# LPDDR4.net
KiCad netlist of a schematic drawn in Altium Designer
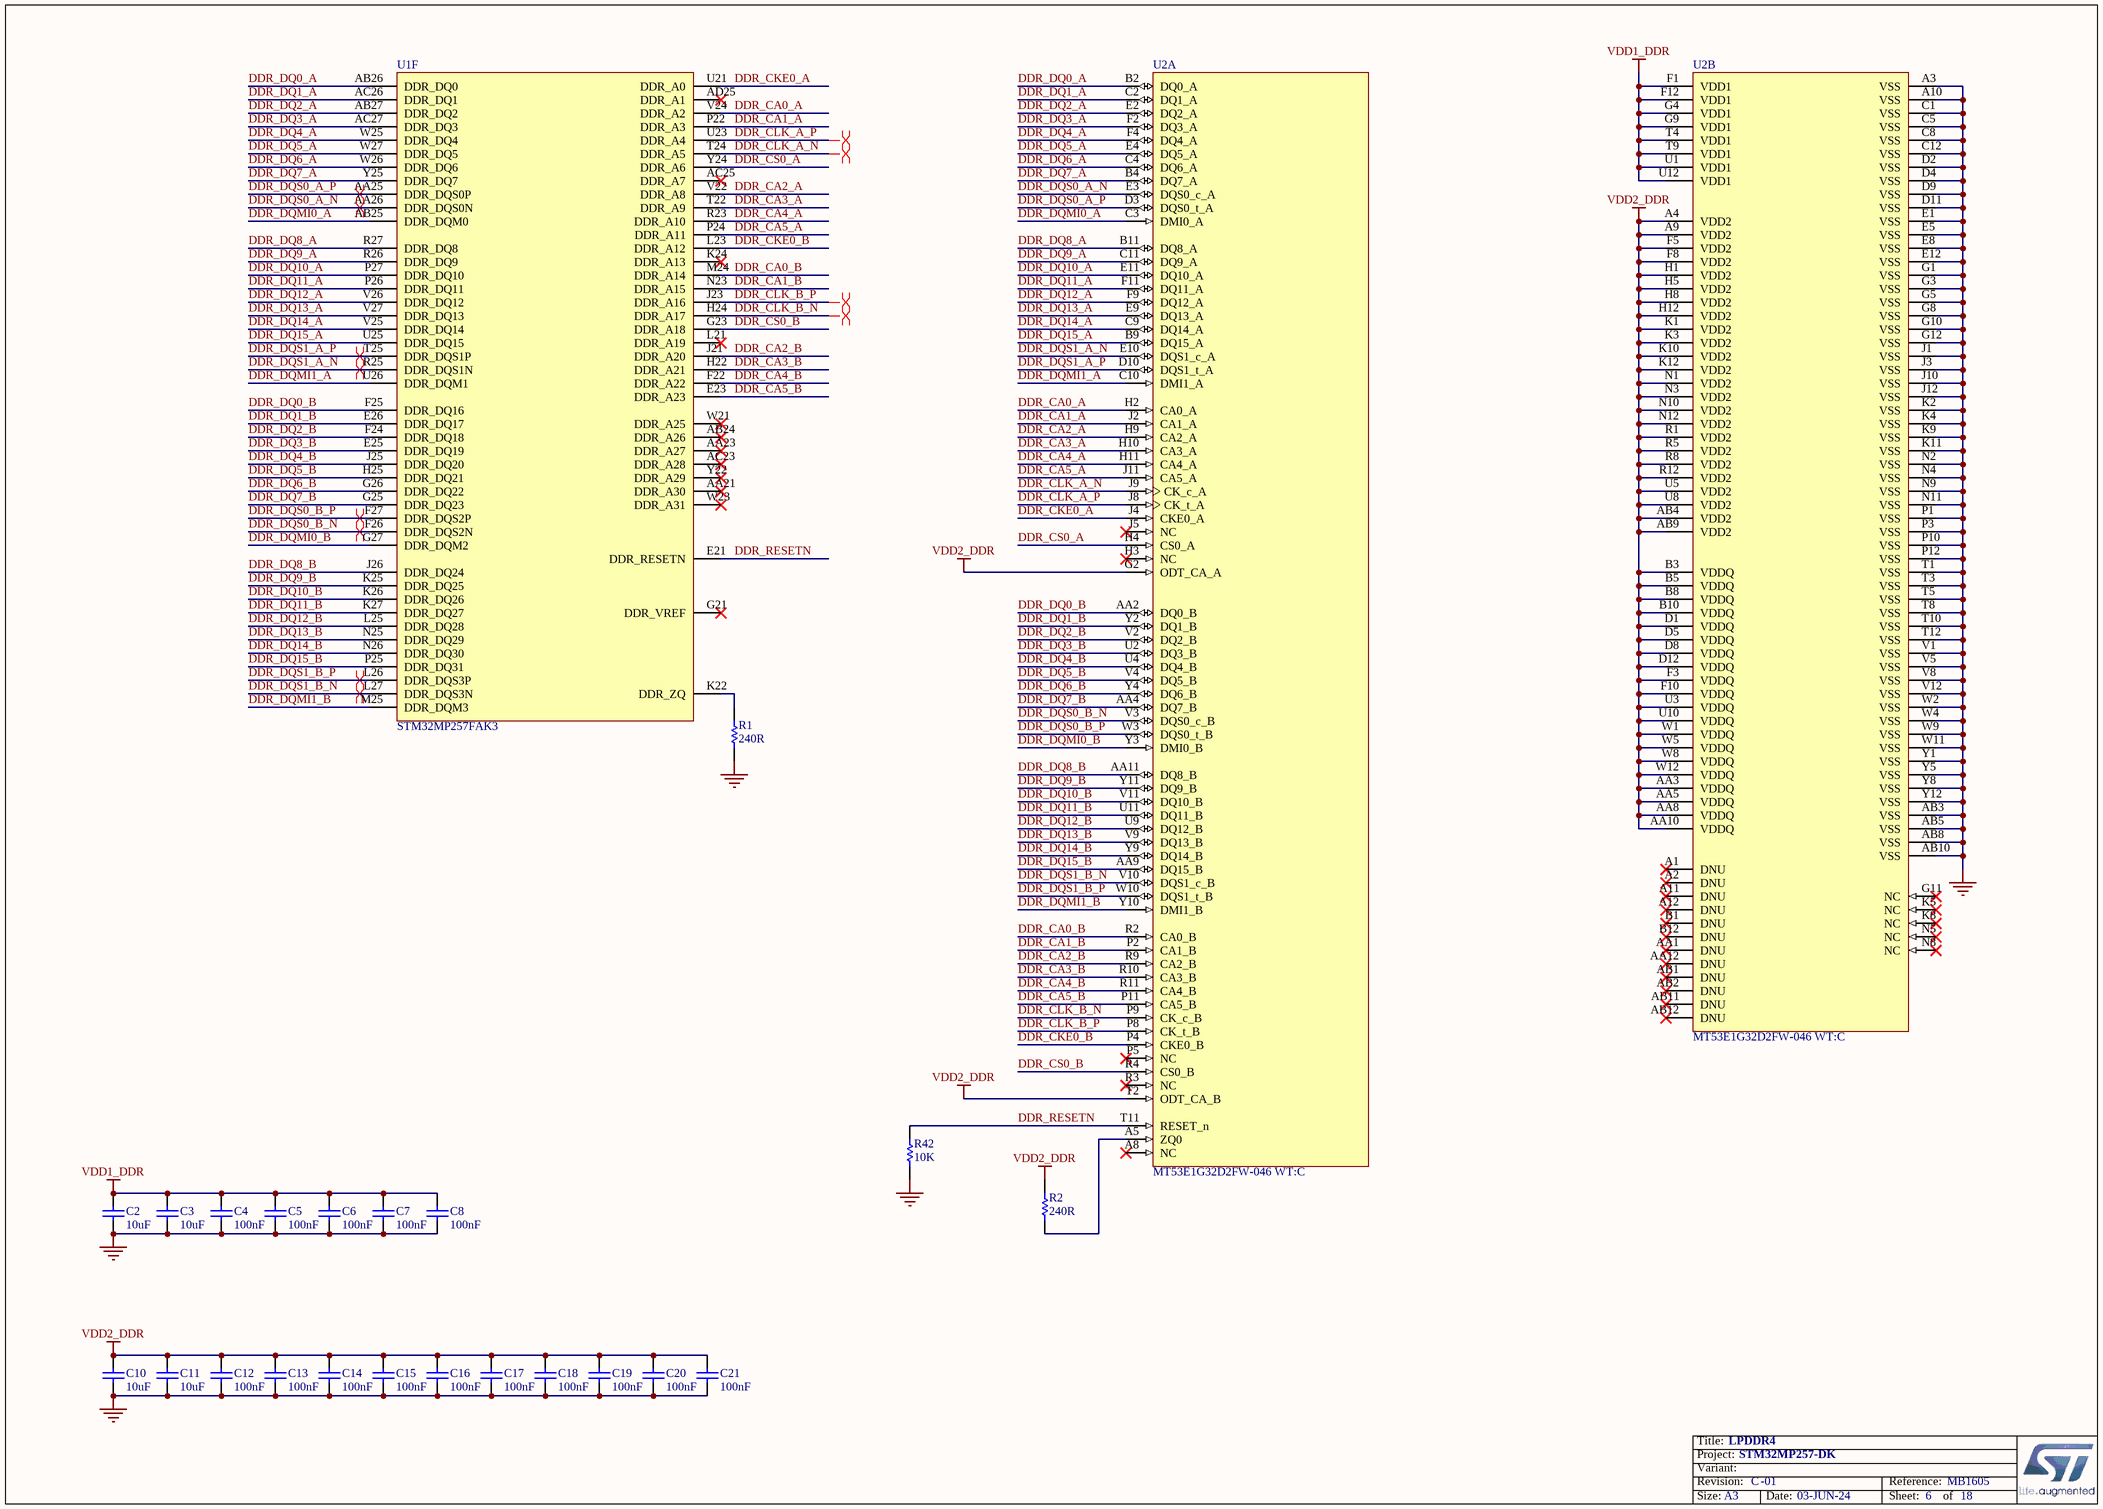
[diagram p0: LPDDR4.SchDoc]

(export (version "E")
  (design (tool "Eeschema 10.0.6"))
  (components
    (comp (ref "C2")
      (value "10uF")
      (footprint "C0603")
      (description "Capacitor, MLCC, 10uF, 6V3, X5R, 20%, 0603, T=0,8mm")
      (fields
        (field (name "INTERNAL_PART_NUMBER") "MCD-01341")
        (field (name "MANUFACTURER_PART_NUMBER") "GRM188R60J106ME47D")
        (field (name "PROVIDED_BY") "SUBCO")
      )
      (libsource (lib "MCD_PARTS_database") (part "Capacitor"))
    )
    (comp (ref "C3")
      (value "10uF")
      (footprint "C0603")
      (description "Capacitor, MLCC, 10uF, 6V3, X5R, 20%, 0603, T=0,8mm")
      (fields
        (field (name "INTERNAL_PART_NUMBER") "MCD-01341")
        (field (name "MANUFACTURER_PART_NUMBER") "GRM188R60J106ME47D")
        (field (name "PROVIDED_BY") "SUBCO")
      )
      (libsource (lib "MCD_PARTS_database") (part "Capacitor"))
    )
    (comp (ref "C4")
      (value "100nF")
      (footprint "C0402")
      (description "Capacitor, MLCC, 100nF, 16V, X7R, +/-10%, 0402, T=0.5mm")
      (fields (field (name "INTERNAL_PART_NUMBER") "MCD-00006") (field (name "MANUFACTURER") "YAGEO"))
      (libsource (lib "MCD_PARTS_database") (part "Capacitor"))
    )
    (comp (ref "C5")
      (value "100nF")
      (footprint "C0402")
      (description "Capacitor, MLCC, 100nF, 16V, X7R, +/-10%, 0402, T=0.5mm")
      (fields (field (name "INTERNAL_PART_NUMBER") "MCD-00006") (field (name "MANUFACTURER") "YAGEO"))
      (libsource (lib "MCD_PARTS_database") (part "Capacitor"))
    )
    (comp (ref "C6")
      (value "100nF")
      (footprint "C0402")
      (description "Capacitor, MLCC, 100nF, 16V, X7R, +/-10%, 0402, T=0.5mm")
      (fields (field (name "INTERNAL_PART_NUMBER") "MCD-00006") (field (name "MANUFACTURER") "YAGEO"))
      (libsource (lib "MCD_PARTS_database") (part "Capacitor"))
    )
    (comp (ref "C7")
      (value "100nF")
      (footprint "C0402")
      (description "Capacitor, MLCC, 100nF, 16V, X7R, +/-10%, 0402, T=0.5mm")
      (fields (field (name "INTERNAL_PART_NUMBER") "MCD-00006") (field (name "MANUFACTURER") "YAGEO"))
      (libsource (lib "MCD_PARTS_database") (part "Capacitor"))
    )
    (comp (ref "C8")
      (value "100nF")
      (footprint "C0402")
      (description "Capacitor, MLCC, 100nF, 16V, X7R, +/-10%, 0402, T=0.5mm")
      (fields (field (name "INTERNAL_PART_NUMBER") "MCD-00006") (field (name "MANUFACTURER") "YAGEO"))
      (libsource (lib "MCD_PARTS_database") (part "Capacitor"))
    )
    (comp (ref "C10")
      (value "10uF")
      (footprint "C0603")
      (description "Capacitor, MLCC, 10uF, 6V3, X5R, 20%, 0603, T=0,8mm")
      (fields
        (field (name "INTERNAL_PART_NUMBER") "MCD-01341")
        (field (name "MANUFACTURER_PART_NUMBER") "GRM188R60J106ME47D")
        (field (name "PROVIDED_BY") "SUBCO")
      )
      (libsource (lib "MCD_PARTS_database") (part "Capacitor"))
    )
    (comp (ref "C11")
      (value "10uF")
      (footprint "C0603")
      (description "Capacitor, MLCC, 10uF, 6V3, X5R, 20%, 0603, T=0,8mm")
      (fields
        (field (name "INTERNAL_PART_NUMBER") "MCD-01341")
        (field (name "MANUFACTURER_PART_NUMBER") "GRM188R60J106ME47D")
        (field (name "PROVIDED_BY") "SUBCO")
      )
      (libsource (lib "MCD_PARTS_database") (part "Capacitor"))
    )
    (comp (ref "C12")
      (value "100nF")
      (footprint "C0402")
      (description "Capacitor, MLCC, 100nF, 16V, X7R, +/-10%, 0402, T=0.5mm")
      (fields (field (name "INTERNAL_PART_NUMBER") "MCD-00006") (field (name "MANUFACTURER") "YAGEO"))
      (libsource (lib "MCD_PARTS_database") (part "Capacitor"))
    )
    (comp (ref "C13")
      (value "100nF")
      (footprint "C0402")
      (description "Capacitor, MLCC, 100nF, 16V, X7R, +/-10%, 0402, T=0.5mm")
      (fields (field (name "INTERNAL_PART_NUMBER") "MCD-00006") (field (name "MANUFACTURER") "YAGEO"))
      (libsource (lib "MCD_PARTS_database") (part "Capacitor"))
    )
    (comp (ref "C14")
      (value "100nF")
      (footprint "C0402")
      (description "Capacitor, MLCC, 100nF, 16V, X7R, +/-10%, 0402, T=0.5mm")
      (fields (field (name "INTERNAL_PART_NUMBER") "MCD-00006") (field (name "MANUFACTURER") "YAGEO"))
      (libsource (lib "MCD_PARTS_database") (part "Capacitor"))
    )
    (comp (ref "C15")
      (value "100nF")
      (footprint "C0402")
      (description "Capacitor, MLCC, 100nF, 16V, X7R, +/-10%, 0402, T=0.5mm")
      (fields (field (name "INTERNAL_PART_NUMBER") "MCD-00006") (field (name "MANUFACTURER") "YAGEO"))
      (libsource (lib "MCD_PARTS_database") (part "Capacitor"))
    )
    (comp (ref "C16")
      (value "100nF")
      (footprint "C0402")
      (description "Capacitor, MLCC, 100nF, 16V, X7R, +/-10%, 0402, T=0.5mm")
      (fields (field (name "INTERNAL_PART_NUMBER") "MCD-00006") (field (name "MANUFACTURER") "YAGEO"))
      (libsource (lib "MCD_PARTS_database") (part "Capacitor"))
    )
    (comp (ref "C17")
      (value "100nF")
      (footprint "C0402")
      (description "Capacitor, MLCC, 100nF, 16V, X7R, +/-10%, 0402, T=0.5mm")
      (fields (field (name "INTERNAL_PART_NUMBER") "MCD-00006") (field (name "MANUFACTURER") "YAGEO"))
      (libsource (lib "MCD_PARTS_database") (part "Capacitor"))
    )
    (comp (ref "C18")
      (value "100nF")
      (footprint "C0402")
      (description "Capacitor, MLCC, 100nF, 16V, X7R, +/-10%, 0402, T=0.5mm")
      (fields (field (name "INTERNAL_PART_NUMBER") "MCD-00006") (field (name "MANUFACTURER") "YAGEO"))
      (libsource (lib "MCD_PARTS_database") (part "Capacitor"))
    )
    (comp (ref "C19")
      (value "100nF")
      (footprint "C0402")
      (description "Capacitor, MLCC, 100nF, 16V, X7R, +/-10%, 0402, T=0.5mm")
      (fields (field (name "INTERNAL_PART_NUMBER") "MCD-00006") (field (name "MANUFACTURER") "YAGEO"))
      (libsource (lib "MCD_PARTS_database") (part "Capacitor"))
    )
    (comp (ref "C20")
      (value "100nF")
      (footprint "C0402")
      (description "Capacitor, MLCC, 100nF, 16V, X7R, +/-10%, 0402, T=0.5mm")
      (fields (field (name "INTERNAL_PART_NUMBER") "MCD-00006") (field (name "MANUFACTURER") "YAGEO"))
      (libsource (lib "MCD_PARTS_database") (part "Capacitor"))
    )
    (comp (ref "C21")
      (value "100nF")
      (footprint "C0402")
      (description "Capacitor, MLCC, 100nF, 16V, X7R, +/-10%, 0402, T=0.5mm")
      (fields (field (name "INTERNAL_PART_NUMBER") "MCD-00006") (field (name "MANUFACTURER") "YAGEO"))
      (libsource (lib "MCD_PARTS_database") (part "Capacitor"))
    )
    (comp (ref "R1")
      (value "240R")
      (footprint "R0201_H0P23")
      (description "Resistor, 240R, 0201, +/-1%, 1/20W")
      (fields (field (name "INTERNAL_PART_NUMBER") "MCD-02253") (field (name "MANUFACTURER") "YAGEO"))
      (libsource (lib "MCD_PARTS_database") (part "Resistor"))
    )
    (comp (ref "R2")
      (value "240R")
      (footprint "R0201_H0P23")
      (description "Resistor, 240R, 0201, +/-1%, 1/20W")
      (fields (field (name "INTERNAL_PART_NUMBER") "MCD-02253") (field (name "MANUFACTURER") "YAGEO"))
      (libsource (lib "MCD_PARTS_database") (part "Resistor"))
    )
    (comp (ref "R42")
      (value "10K")
      (footprint "R0402")
      (description "Resistor, 10K, 0402, +/-1%, 1/16W")
      (fields (field (name "INTERNAL_PART_NUMBER") "MCD-00053") (field (name "BMS_PART_NUMBER") "9131590"))
      (libsource (lib "MCD_PARTS_database") (part "Resistor"))
    )
    (comp (ref "U1")
      (value "STM32MP257FAK3")
      (footprint "ICC_TFBGA424_14X14_P050_H1P20_CODE-B0A2")
      (description "MPU , 2xCortex-A35@1.5GHz, Cortex-M33@400MHz, TFBGA 14x14, pitch 0.5, 648KB SRAM, With Crypto")
      (fields
        (field (name "INTERNAL_PART_NUMBER") "MCD-03375")
        (field (name "MANUFACTURER") "STMICROELECTRONICS")
      )
      (libsource (lib "MCD_PARTS_database") (part "STM32MP257FAK3"))
    )
    (comp (ref "U2")
      (value "MT53E1G32D2FW-046 WT:C")
      (footprint "ICC_TFBGA200_10X14P5_P080_H1P05_PS0P3")
      (description "Memory, LPDDR4 SDRAM,1V8, 32Gbit, 2133MHz")
      (fields (field (name "INTERNAL_PART_NUMBER") "MCD-04160") (field (name "MANUFACTURER") "MICRON"))
      (libsource (lib "MCD_PARTS_database") (part "MT53E1G32D2FW-046 WT{colon}C"))
    )
  )
  (nets
    (net (code "1") (name "/DDR_CA0_A") (class "Default")
      (node (ref "U1") (pin "V24") (pinfunction "DDR_A2_V24") (pintype "passive"))
      (node (ref "U2") (pin "H2") (pinfunction "CA0_A_H2") (pintype "input"))
    )
    (net (code "2") (name "/DDR_CA0_B") (class "Default")
      (node (ref "U1") (pin "M24") (pinfunction "DDR_A14_M24") (pintype "passive"))
      (node (ref "U2") (pin "R2") (pinfunction "CA0_B_R2") (pintype "input"))
    )
    (net (code "3") (name "/DDR_CA1_A") (class "Default")
      (node (ref "U1") (pin "P22") (pinfunction "DDR_A3_P22") (pintype "passive"))
      (node (ref "U2") (pin "J2") (pinfunction "CA1_A_J2") (pintype "input"))
    )
    (net (code "4") (name "/DDR_CA1_B") (class "Default")
      (node (ref "U1") (pin "N23") (pinfunction "DDR_A15_N23") (pintype "passive"))
      (node (ref "U2") (pin "P2") (pinfunction "CA1_B_P2") (pintype "input"))
    )
    (net (code "5") (name "/DDR_CA2_A") (class "Default")
      (node (ref "U1") (pin "V22") (pinfunction "DDR_A8_V22") (pintype "passive"))
      (node (ref "U2") (pin "H9") (pinfunction "CA2_A_H9") (pintype "input"))
    )
    (net (code "6") (name "/DDR_CA2_B") (class "Default")
      (node (ref "U1") (pin "J21") (pinfunction "DDR_A20_J21") (pintype "passive"))
      (node (ref "U2") (pin "R9") (pinfunction "CA2_B_R9") (pintype "input"))
    )
    (net (code "7") (name "/DDR_CA3_A") (class "Default")
      (node (ref "U1") (pin "T22") (pinfunction "DDR_A9_T22") (pintype "passive"))
      (node (ref "U2") (pin "H10") (pinfunction "CA3_A_H10") (pintype "input"))
    )
    (net (code "8") (name "/DDR_CA3_B") (class "Default")
      (node (ref "U1") (pin "H22") (pinfunction "DDR_A21_H22") (pintype "passive"))
      (node (ref "U2") (pin "R10") (pinfunction "CA3_B_R10") (pintype "input"))
    )
    (net (code "9") (name "/DDR_CA4_A") (class "Default")
      (node (ref "U1") (pin "R23") (pinfunction "DDR_A10_R23") (pintype "passive"))
      (node (ref "U2") (pin "H11") (pinfunction "CA4_A_H11") (pintype "input"))
    )
    (net (code "10") (name "/DDR_CA4_B") (class "Default")
      (node (ref "U1") (pin "F22") (pinfunction "DDR_A22_F22") (pintype "passive"))
      (node (ref "U2") (pin "R11") (pinfunction "CA4_B_R11") (pintype "input"))
    )
    (net (code "11") (name "/DDR_CA5_A") (class "Default")
      (node (ref "U1") (pin "P24") (pinfunction "DDR_A11_P24") (pintype "passive"))
      (node (ref "U2") (pin "J11") (pinfunction "CA5_A_J11") (pintype "input"))
    )
    (net (code "12") (name "/DDR_CA5_B") (class "Default")
      (node (ref "U1") (pin "E23") (pinfunction "DDR_A23_E23") (pintype "passive"))
      (node (ref "U2") (pin "P11") (pinfunction "CA5_B_P11") (pintype "input"))
    )
    (net (code "13") (name "/DDR_CKE0_A") (class "Default")
      (node (ref "U1") (pin "U21") (pinfunction "DDR_A0_U21") (pintype "passive"))
      (node (ref "U2") (pin "J4") (pinfunction "CKE0_A_J4") (pintype "input"))
    )
    (net (code "14") (name "/DDR_CKE0_B") (class "Default")
      (node (ref "U1") (pin "L23") (pinfunction "DDR_A12_L23") (pintype "passive"))
      (node (ref "U2") (pin "P4") (pinfunction "CKE0_B_P4") (pintype "input"))
    )
    (net (code "15") (name "/DDR_CLK_A_N") (class "Default")
      (node (ref "U1") (pin "T24") (pinfunction "DDR_A5_T24") (pintype "passive"))
      (node (ref "U2") (pin "J9") (pinfunction "CK_c_A_J9") (pintype "input"))
    )
    (net (code "16") (name "/DDR_CLK_A_P") (class "Default")
      (node (ref "U1") (pin "U23") (pinfunction "DDR_A4_U23") (pintype "passive"))
      (node (ref "U2") (pin "J8") (pinfunction "CK_t_A_J8") (pintype "input"))
    )
    (net (code "17") (name "/DDR_CLK_B_N") (class "Default")
      (node (ref "U1") (pin "H24") (pinfunction "DDR_A17_H24") (pintype "passive"))
      (node (ref "U2") (pin "P9") (pinfunction "CK_c_B_P9") (pintype "input"))
    )
    (net (code "18") (name "/DDR_CLK_B_P") (class "Default")
      (node (ref "U1") (pin "J23") (pinfunction "DDR_A16_J23") (pintype "passive"))
      (node (ref "U2") (pin "P8") (pinfunction "CK_t_B_P8") (pintype "input"))
    )
    (net (code "19") (name "/DDR_CS0_A") (class "Default")
      (node (ref "U1") (pin "Y24") (pinfunction "DDR_A6_Y24") (pintype "passive"))
      (node (ref "U2") (pin "H4") (pinfunction "CS0_A_H4") (pintype "input"))
    )
    (net (code "20") (name "/DDR_CS0_B") (class "Default")
      (node (ref "U1") (pin "G23") (pinfunction "DDR_A18_G23") (pintype "passive"))
      (node (ref "U2") (pin "R4") (pinfunction "CS0_B_R4") (pintype "input"))
    )
    (net (code "21") (name "/DDR_DQ0_A") (class "Default")
      (node (ref "U1") (pin "AB26") (pinfunction "DDR_DQ0_AB26") (pintype "passive"))
      (node (ref "U2") (pin "B2") (pinfunction "DQ0_A_B2") (pintype "bidirectional"))
    )
    (net (code "22") (name "/DDR_DQ0_B") (class "Default")
      (node (ref "U1") (pin "F25") (pinfunction "DDR_DQ16_F25") (pintype "passive"))
      (node (ref "U2") (pin "AA2") (pinfunction "DQ0_B_AA2") (pintype "bidirectional"))
    )
    (net (code "23") (name "/DDR_DQ1_A") (class "Default")
      (node (ref "U1") (pin "AC26") (pinfunction "DDR_DQ1_AC26") (pintype "passive"))
      (node (ref "U2") (pin "C2") (pinfunction "DQ1_A_C2") (pintype "bidirectional"))
    )
    (net (code "24") (name "/DDR_DQ1_B") (class "Default")
      (node (ref "U1") (pin "E26") (pinfunction "DDR_DQ17_E26") (pintype "passive"))
      (node (ref "U2") (pin "Y2") (pinfunction "DQ1_B_Y2") (pintype "bidirectional"))
    )
    (net (code "25") (name "/DDR_DQ2_A") (class "Default")
      (node (ref "U1") (pin "AB27") (pinfunction "DDR_DQ2_AB27") (pintype "passive"))
      (node (ref "U2") (pin "E2") (pinfunction "DQ2_A_E2") (pintype "bidirectional"))
    )
    (net (code "26") (name "/DDR_DQ2_B") (class "Default")
      (node (ref "U1") (pin "F24") (pinfunction "DDR_DQ18_F24") (pintype "passive"))
      (node (ref "U2") (pin "V2") (pinfunction "DQ2_B_V2") (pintype "bidirectional"))
    )
    (net (code "27") (name "/DDR_DQ3_A") (class "Default")
      (node (ref "U1") (pin "AC27") (pinfunction "DDR_DQ3_AC27") (pintype "passive"))
      (node (ref "U2") (pin "F2") (pinfunction "DQ3_A_F2") (pintype "bidirectional"))
    )
    (net (code "28") (name "/DDR_DQ3_B") (class "Default")
      (node (ref "U1") (pin "E25") (pinfunction "DDR_DQ19_E25") (pintype "passive"))
      (node (ref "U2") (pin "U2") (pinfunction "DQ3_B_U2") (pintype "bidirectional"))
    )
    (net (code "29") (name "/DDR_DQ4_A") (class "Default")
      (node (ref "U1") (pin "W25") (pinfunction "DDR_DQ4_W25") (pintype "passive"))
      (node (ref "U2") (pin "F4") (pinfunction "DQ4_A_F4") (pintype "bidirectional"))
    )
    (net (code "30") (name "/DDR_DQ4_B") (class "Default")
      (node (ref "U1") (pin "J25") (pinfunction "DDR_DQ20_J25") (pintype "passive"))
      (node (ref "U2") (pin "U4") (pinfunction "DQ4_B_U4") (pintype "bidirectional"))
    )
    (net (code "31") (name "/DDR_DQ5_A") (class "Default")
      (node (ref "U1") (pin "W27") (pinfunction "DDR_DQ5_W27") (pintype "passive"))
      (node (ref "U2") (pin "E4") (pinfunction "DQ5_A_E4") (pintype "bidirectional"))
    )
    (net (code "32") (name "/DDR_DQ5_B") (class "Default")
      (node (ref "U1") (pin "H25") (pinfunction "DDR_DQ21_H25") (pintype "passive"))
      (node (ref "U2") (pin "V4") (pinfunction "DQ5_B_V4") (pintype "bidirectional"))
    )
    (net (code "33") (name "/DDR_DQ6_A") (class "Default")
      (node (ref "U1") (pin "W26") (pinfunction "DDR_DQ6_W26") (pintype "passive"))
      (node (ref "U2") (pin "C4") (pinfunction "DQ6_A_C4") (pintype "bidirectional"))
    )
    (net (code "34") (name "/DDR_DQ6_B") (class "Default")
      (node (ref "U1") (pin "G26") (pinfunction "DDR_DQ22_G26") (pintype "passive"))
      (node (ref "U2") (pin "Y4") (pinfunction "DQ6_B_Y4") (pintype "bidirectional"))
    )
    (net (code "35") (name "/DDR_DQ7_A") (class "Default")
      (node (ref "U1") (pin "Y25") (pinfunction "DDR_DQ7_Y25") (pintype "passive"))
      (node (ref "U2") (pin "B4") (pinfunction "DQ7_A_B4") (pintype "bidirectional"))
    )
    (net (code "36") (name "/DDR_DQ7_B") (class "Default")
      (node (ref "U1") (pin "G25") (pinfunction "DDR_DQ23_G25") (pintype "passive"))
      (node (ref "U2") (pin "AA4") (pinfunction "DQ7_B_AA4") (pintype "bidirectional"))
    )
    (net (code "37") (name "/DDR_DQ8_A") (class "Default")
      (node (ref "U1") (pin "R27") (pinfunction "DDR_DQ8_R27") (pintype "passive"))
      (node (ref "U2") (pin "B11") (pinfunction "DQ8_A_B11") (pintype "bidirectional"))
    )
    (net (code "38") (name "/DDR_DQ8_B") (class "Default")
      (node (ref "U1") (pin "J26") (pinfunction "DDR_DQ24_J26") (pintype "passive"))
      (node (ref "U2") (pin "AA11") (pinfunction "DQ8_B_AA11") (pintype "bidirectional"))
    )
    (net (code "39") (name "/DDR_DQ9_A") (class "Default")
      (node (ref "U1") (pin "R26") (pinfunction "DDR_DQ9_R26") (pintype "passive"))
      (node (ref "U2") (pin "C11") (pinfunction "DQ9_A_C11") (pintype "bidirectional"))
    )
    (net (code "40") (name "/DDR_DQ9_B") (class "Default")
      (node (ref "U1") (pin "K25") (pinfunction "DDR_DQ25_K25") (pintype "passive"))
      (node (ref "U2") (pin "Y11") (pinfunction "DQ9_B_Y11") (pintype "bidirectional"))
    )
    (net (code "41") (name "/DDR_DQ10_A") (class "Default")
      (node (ref "U1") (pin "P27") (pinfunction "DDR_DQ10_P27") (pintype "passive"))
      (node (ref "U2") (pin "E11") (pinfunction "DQ10_A_E11") (pintype "bidirectional"))
    )
    (net (code "42") (name "/DDR_DQ10_B") (class "Default")
      (node (ref "U1") (pin "K26") (pinfunction "DDR_DQ26_K26") (pintype "passive"))
      (node (ref "U2") (pin "V11") (pinfunction "DQ10_B_V11") (pintype "bidirectional"))
    )
    (net (code "43") (name "/DDR_DQ11_A") (class "Default")
      (node (ref "U1") (pin "P26") (pinfunction "DDR_DQ11_P26") (pintype "passive"))
      (node (ref "U2") (pin "F11") (pinfunction "DQ11_A_F11") (pintype "bidirectional"))
    )
    (net (code "44") (name "/DDR_DQ11_B") (class "Default")
      (node (ref "U1") (pin "K27") (pinfunction "DDR_DQ27_K27") (pintype "passive"))
      (node (ref "U2") (pin "U11") (pinfunction "DQ11_B_U11") (pintype "bidirectional"))
    )
    (net (code "45") (name "/DDR_DQ12_A") (class "Default")
      (node (ref "U1") (pin "V26") (pinfunction "DDR_DQ12_V26") (pintype "passive"))
      (node (ref "U2") (pin "F9") (pinfunction "DQ12_A_F9") (pintype "bidirectional"))
    )
    (net (code "46") (name "/DDR_DQ12_B") (class "Default")
      (node (ref "U1") (pin "L25") (pinfunction "DDR_DQ28_L25") (pintype "passive"))
      (node (ref "U2") (pin "U9") (pinfunction "DQ12_B_U9") (pintype "bidirectional"))
    )
    (net (code "47") (name "/DDR_DQ13_A") (class "Default")
      (node (ref "U1") (pin "V27") (pinfunction "DDR_DQ13_V27") (pintype "passive"))
      (node (ref "U2") (pin "E9") (pinfunction "DQ13_A_E9") (pintype "bidirectional"))
    )
    (net (code "48") (name "/DDR_DQ13_B") (class "Default")
      (node (ref "U1") (pin "N25") (pinfunction "DDR_DQ29_N25") (pintype "passive"))
      (node (ref "U2") (pin "V9") (pinfunction "DQ13_B_V9") (pintype "bidirectional"))
    )
    (net (code "49") (name "/DDR_DQ14_A") (class "Default")
      (node (ref "U1") (pin "V25") (pinfunction "DDR_DQ14_V25") (pintype "passive"))
      (node (ref "U2") (pin "C9") (pinfunction "DQ14_A_C9") (pintype "bidirectional"))
    )
    (net (code "50") (name "/DDR_DQ14_B") (class "Default")
      (node (ref "U1") (pin "N26") (pinfunction "DDR_DQ30_N26") (pintype "passive"))
      (node (ref "U2") (pin "Y9") (pinfunction "DQ14_B_Y9") (pintype "bidirectional"))
    )
    (net (code "51") (name "/DDR_DQ15_A") (class "Default")
      (node (ref "U1") (pin "U25") (pinfunction "DDR_DQ15_U25") (pintype "passive"))
      (node (ref "U2") (pin "B9") (pinfunction "DQ15_A_B9") (pintype "bidirectional"))
    )
    (net (code "52") (name "/DDR_DQ15_B") (class "Default")
      (node (ref "U1") (pin "P25") (pinfunction "DDR_DQ31_P25") (pintype "passive"))
      (node (ref "U2") (pin "AA9") (pinfunction "DQ15_B_AA9") (pintype "bidirectional"))
    )
    (net (code "53") (name "/DDR_DQMI0_A") (class "Default")
      (node (ref "U1") (pin "AB25") (pinfunction "DDR_DQM0_AB25") (pintype "passive"))
      (node (ref "U2") (pin "C3") (pinfunction "DMI0_A_C3") (pintype "input"))
    )
    (net (code "54") (name "/DDR_DQMI0_B") (class "Default")
      (node (ref "U1") (pin "G27") (pinfunction "DDR_DQM2_G27") (pintype "passive"))
      (node (ref "U2") (pin "Y3") (pinfunction "DMI0_B_Y3") (pintype "input"))
    )
    (net (code "55") (name "/DDR_DQMI1_A") (class "Default")
      (node (ref "U1") (pin "U26") (pinfunction "DDR_DQM1_U26") (pintype "passive"))
      (node (ref "U2") (pin "C10") (pinfunction "DMI1_A_C10") (pintype "input"))
    )
    (net (code "56") (name "/DDR_DQMI1_B") (class "Default")
      (node (ref "U1") (pin "M25") (pinfunction "DDR_DQM3_M25") (pintype "passive"))
      (node (ref "U2") (pin "Y10") (pinfunction "DMI1_B_Y10") (pintype "input"))
    )
    (net (code "57") (name "/DDR_DQS0_A_N") (class "Default")
      (node (ref "U1") (pin "AA26") (pinfunction "DDR_DQS0N_AA26") (pintype "passive"))
      (node (ref "U2") (pin "E3") (pinfunction "DQS0_c_A_E3") (pintype "bidirectional"))
    )
    (net (code "58") (name "/DDR_DQS0_A_P") (class "Default")
      (node (ref "U1") (pin "AA25") (pinfunction "DDR_DQS0P_AA25") (pintype "passive"))
      (node (ref "U2") (pin "D3") (pinfunction "DQS0_t_A_D3") (pintype "bidirectional"))
    )
    (net (code "59") (name "/DDR_DQS0_B_N") (class "Default")
      (node (ref "U1") (pin "F26") (pinfunction "DDR_DQS2N_F26") (pintype "passive"))
      (node (ref "U2") (pin "V3") (pinfunction "DQS0_c_B_V3") (pintype "bidirectional"))
    )
    (net (code "60") (name "/DDR_DQS0_B_P") (class "Default")
      (node (ref "U1") (pin "F27") (pinfunction "DDR_DQS2P_F27") (pintype "passive"))
      (node (ref "U2") (pin "W3") (pinfunction "DQS0_t_B_W3") (pintype "bidirectional"))
    )
    (net (code "61") (name "/DDR_DQS1_A_N") (class "Default")
      (node (ref "U1") (pin "R25") (pinfunction "DDR_DQS1N_R25") (pintype "passive"))
      (node (ref "U2") (pin "E10") (pinfunction "DQS1_c_A_E10") (pintype "bidirectional"))
    )
    (net (code "62") (name "/DDR_DQS1_A_P") (class "Default")
      (node (ref "U1") (pin "T25") (pinfunction "DDR_DQS1P_T25") (pintype "passive"))
      (node (ref "U2") (pin "D10") (pinfunction "DQS1_t_A_D10") (pintype "bidirectional"))
    )
    (net (code "63") (name "/DDR_DQS1_B_N") (class "Default")
      (node (ref "U1") (pin "L27") (pinfunction "DDR_DQS3N_L27") (pintype "passive"))
      (node (ref "U2") (pin "V10") (pinfunction "DQS1_c_B_V10") (pintype "bidirectional"))
    )
    (net (code "64") (name "/DDR_DQS1_B_P") (class "Default")
      (node (ref "U1") (pin "L26") (pinfunction "DDR_DQS3P_L26") (pintype "passive"))
      (node (ref "U2") (pin "W10") (pinfunction "DQS1_t_B_W10") (pintype "bidirectional"))
    )
    (net (code "65") (name "/DDR_RESETN") (class "Default")
      (node (ref "R42") (pin "2") (pinfunction "2_2") (pintype "passive"))
      (node (ref "U1") (pin "E21") (pinfunction "DDR_RESETN_E21") (pintype "passive"))
      (node (ref "U2") (pin "T11") (pinfunction "RESET_n_T11") (pintype "input"))
    )
    (net (code "66") (name "GND") (class "Default")
      (node (ref "C10") (pin "1") (pinfunction "1_1") (pintype "passive"))
      (node (ref "C11") (pin "1") (pinfunction "1_1") (pintype "passive"))
      (node (ref "C12") (pin "2") (pinfunction "2_2") (pintype "passive"))
      (node (ref "C13") (pin "2") (pinfunction "2_2") (pintype "passive"))
      (node (ref "C14") (pin "2") (pinfunction "2_2") (pintype "passive"))
      (node (ref "C15") (pin "2") (pinfunction "2_2") (pintype "passive"))
      (node (ref "C16") (pin "2") (pinfunction "2_2") (pintype "passive"))
      (node (ref "C17") (pin "2") (pinfunction "2_2") (pintype "passive"))
      (node (ref "C18") (pin "2") (pinfunction "2_2") (pintype "passive"))
      (node (ref "C19") (pin "2") (pinfunction "2_2") (pintype "passive"))
      (node (ref "C2") (pin "1") (pinfunction "1_1") (pintype "passive"))
      (node (ref "C20") (pin "2") (pinfunction "2_2") (pintype "passive"))
      (node (ref "C21") (pin "2") (pinfunction "2_2") (pintype "passive"))
      (node (ref "C3") (pin "1") (pinfunction "1_1") (pintype "passive"))
      (node (ref "C4") (pin "2") (pinfunction "2_2") (pintype "passive"))
      (node (ref "C5") (pin "2") (pinfunction "2_2") (pintype "passive"))
      (node (ref "C6") (pin "2") (pinfunction "2_2") (pintype "passive"))
      (node (ref "C7") (pin "2") (pinfunction "2_2") (pintype "passive"))
      (node (ref "C8") (pin "2") (pinfunction "2_2") (pintype "passive"))
      (node (ref "R1") (pin "1") (pinfunction "1_1") (pintype "passive"))
      (node (ref "R42") (pin "1") (pinfunction "1_1") (pintype "passive"))
      (node (ref "U2") (pin "A10") (pinfunction "VSS_A10") (pintype "power_in"))
      (node (ref "U2") (pin "A3") (pinfunction "VSS_A3") (pintype "power_in"))
      (node (ref "U2") (pin "AB10") (pinfunction "VSS_AB10") (pintype "passive"))
      (node (ref "U2") (pin "AB3") (pinfunction "VSS_AB3") (pintype "passive"))
      (node (ref "U2") (pin "AB5") (pinfunction "VSS_AB5") (pintype "passive"))
      (node (ref "U2") (pin "AB8") (pinfunction "VSS_AB8") (pintype "passive"))
      (node (ref "U2") (pin "C1") (pinfunction "VSS_C1") (pintype "power_in"))
      (node (ref "U2") (pin "C12") (pinfunction "VSS_C12") (pintype "power_in"))
      (node (ref "U2") (pin "C5") (pinfunction "VSS_C5") (pintype "power_in"))
      (node (ref "U2") (pin "C8") (pinfunction "VSS_C8") (pintype "power_in"))
      (node (ref "U2") (pin "D11") (pinfunction "VSS_D11") (pintype "power_in"))
      (node (ref "U2") (pin "D2") (pinfunction "VSS_D2") (pintype "power_in"))
      (node (ref "U2") (pin "D4") (pinfunction "VSS_D4") (pintype "power_in"))
      (node (ref "U2") (pin "D9") (pinfunction "VSS_D9") (pintype "power_in"))
      (node (ref "U2") (pin "E1") (pinfunction "VSS_E1") (pintype "power_in"))
      (node (ref "U2") (pin "E12") (pinfunction "VSS_E12") (pintype "power_in"))
      (node (ref "U2") (pin "E5") (pinfunction "VSS_E5") (pintype "power_in"))
      (node (ref "U2") (pin "E8") (pinfunction "VSS_E8") (pintype "power_in"))
      (node (ref "U2") (pin "G1") (pinfunction "VSS_G1") (pintype "power_in"))
      (node (ref "U2") (pin "G10") (pinfunction "VSS_G10") (pintype "power_in"))
      (node (ref "U2") (pin "G12") (pinfunction "VSS_G12") (pintype "power_in"))
      (node (ref "U2") (pin "G3") (pinfunction "VSS_G3") (pintype "power_in"))
      (node (ref "U2") (pin "G5") (pinfunction "VSS_G5") (pintype "power_in"))
      (node (ref "U2") (pin "G8") (pinfunction "VSS_G8") (pintype "power_in"))
      (node (ref "U2") (pin "J1") (pinfunction "VSS_J1") (pintype "power_in"))
      (node (ref "U2") (pin "J10") (pinfunction "VSS_J10") (pintype "power_in"))
      (node (ref "U2") (pin "J12") (pinfunction "VSS_J12") (pintype "power_in"))
      (node (ref "U2") (pin "J3") (pinfunction "VSS_J3") (pintype "power_in"))
      (node (ref "U2") (pin "K11") (pinfunction "VSS_K11") (pintype "passive"))
      (node (ref "U2") (pin "K2") (pinfunction "VSS_K2") (pintype "power_in"))
      (node (ref "U2") (pin "K4") (pinfunction "VSS_K4") (pintype "power_in"))
      (node (ref "U2") (pin "K9") (pinfunction "VSS_K9") (pintype "power_in"))
      (node (ref "U2") (pin "N11") (pinfunction "VSS_N11") (pintype "passive"))
      (node (ref "U2") (pin "N2") (pinfunction "VSS_N2") (pintype "passive"))
      (node (ref "U2") (pin "N4") (pinfunction "VSS_N4") (pintype "passive"))
      (node (ref "U2") (pin "N9") (pinfunction "VSS_N9") (pintype "passive"))
      (node (ref "U2") (pin "P1") (pinfunction "VSS_P1") (pintype "passive"))
      (node (ref "U2") (pin "P10") (pinfunction "VSS_P10") (pintype "power_in"))
      (node (ref "U2") (pin "P12") (pinfunction "VSS_P12") (pintype "passive"))
      (node (ref "U2") (pin "P3") (pinfunction "VSS_P3") (pintype "power_in"))
      (node (ref "U2") (pin "T1") (pinfunction "VSS_T1") (pintype "passive"))
      (node (ref "U2") (pin "T10") (pinfunction "VSS_T10") (pintype "passive"))
      (node (ref "U2") (pin "T12") (pinfunction "VSS_T12") (pintype "passive"))
      (node (ref "U2") (pin "T3") (pinfunction "VSS_T3") (pintype "passive"))
      (node (ref "U2") (pin "T5") (pinfunction "VSS_T5") (pintype "passive"))
      (node (ref "U2") (pin "T8") (pinfunction "VSS_T8") (pintype "passive"))
      (node (ref "U2") (pin "V1") (pinfunction "VSS_V1") (pintype "power_in"))
      (node (ref "U2") (pin "V12") (pinfunction "VSS_V12") (pintype "passive"))
      (node (ref "U2") (pin "V5") (pinfunction "VSS_V5") (pintype "power_in"))
      (node (ref "U2") (pin "V8") (pinfunction "VSS_V8") (pintype "passive"))
      (node (ref "U2") (pin "W11") (pinfunction "VSS_W11") (pintype "passive"))
      (node (ref "U2") (pin "W2") (pinfunction "VSS_W2") (pintype "passive"))
      (node (ref "U2") (pin "W4") (pinfunction "VSS_W4") (pintype "passive"))
      (node (ref "U2") (pin "W9") (pinfunction "VSS_W9") (pintype "passive"))
      (node (ref "U2") (pin "Y1") (pinfunction "VSS_Y1") (pintype "passive"))
      (node (ref "U2") (pin "Y12") (pinfunction "VSS_Y12") (pintype "passive"))
      (node (ref "U2") (pin "Y5") (pinfunction "VSS_Y5") (pintype "passive"))
      (node (ref "U2") (pin "Y8") (pinfunction "VSS_Y8") (pintype "passive"))
    )
    (net (code "67") (name "Net-(U1F-DDR_ZQ)") (class "Default")
      (node (ref "R1") (pin "2") (pinfunction "2_2") (pintype "passive"))
      (node (ref "U1") (pin "K22") (pinfunction "DDR_ZQ_K22") (pintype "passive"))
    )
    (net (code "68") (name "Net-(U2A-ZQ0)") (class "Default")
      (node (ref "R2") (pin "1") (pinfunction "1_1") (pintype "passive"))
      (node (ref "U2") (pin "A5") (pinfunction "ZQ0_A5") (pintype "input"))
    )
    (net (code "69") (name "VDD1_DDR") (class "Default")
      (node (ref "C2") (pin "2") (pinfunction "2_2") (pintype "passive"))
      (node (ref "C3") (pin "2") (pinfunction "2_2") (pintype "passive"))
      (node (ref "C4") (pin "1") (pinfunction "1_1") (pintype "passive"))
      (node (ref "C5") (pin "1") (pinfunction "1_1") (pintype "passive"))
      (node (ref "C6") (pin "1") (pinfunction "1_1") (pintype "passive"))
      (node (ref "C7") (pin "1") (pinfunction "1_1") (pintype "passive"))
      (node (ref "C8") (pin "1") (pinfunction "1_1") (pintype "passive"))
      (node (ref "U2") (pin "F1") (pinfunction "VDD1_F1") (pintype "power_in"))
      (node (ref "U2") (pin "F12") (pinfunction "VDD1_F12") (pintype "power_in"))
      (node (ref "U2") (pin "G4") (pinfunction "VDD1_G4") (pintype "power_in"))
      (node (ref "U2") (pin "G9") (pinfunction "VDD1_G9") (pintype "power_in"))
      (node (ref "U2") (pin "T4") (pinfunction "VDD1_T4") (pintype "power_in"))
      (node (ref "U2") (pin "T9") (pinfunction "VDD1_T9") (pintype "power_in"))
      (node (ref "U2") (pin "U1") (pinfunction "VDD1_U1") (pintype "power_in"))
      (node (ref "U2") (pin "U12") (pinfunction "VDD1_U12") (pintype "power_in"))
    )
    (net (code "70") (name "VDD2_DDR") (class "Default")
      (node (ref "C10") (pin "2") (pinfunction "2_2") (pintype "passive"))
      (node (ref "C11") (pin "2") (pinfunction "2_2") (pintype "passive"))
      (node (ref "C12") (pin "1") (pinfunction "1_1") (pintype "passive"))
      (node (ref "C13") (pin "1") (pinfunction "1_1") (pintype "passive"))
      (node (ref "C14") (pin "1") (pinfunction "1_1") (pintype "passive"))
      (node (ref "C15") (pin "1") (pinfunction "1_1") (pintype "passive"))
      (node (ref "C16") (pin "1") (pinfunction "1_1") (pintype "passive"))
      (node (ref "C17") (pin "1") (pinfunction "1_1") (pintype "passive"))
      (node (ref "C18") (pin "1") (pinfunction "1_1") (pintype "passive"))
      (node (ref "C19") (pin "1") (pinfunction "1_1") (pintype "passive"))
      (node (ref "C20") (pin "1") (pinfunction "1_1") (pintype "passive"))
      (node (ref "C21") (pin "1") (pinfunction "1_1") (pintype "passive"))
      (node (ref "R2") (pin "2") (pinfunction "2_2") (pintype "passive"))
      (node (ref "U2") (pin "A4") (pinfunction "VDD2_A4") (pintype "power_in"))
      (node (ref "U2") (pin "A9") (pinfunction "VDD2_A9") (pintype "power_in"))
      (node (ref "U2") (pin "AA10") (pinfunction "VDDQ_AA10") (pintype "power_in"))
      (node (ref "U2") (pin "AA3") (pinfunction "VDDQ_AA3") (pintype "power_in"))
      (node (ref "U2") (pin "AA5") (pinfunction "VDDQ_AA5") (pintype "power_in"))
      (node (ref "U2") (pin "AA8") (pinfunction "VDDQ_AA8") (pintype "power_in"))
      (node (ref "U2") (pin "AB4") (pinfunction "VDD2_AB4") (pintype "power_in"))
      (node (ref "U2") (pin "AB9") (pinfunction "VDD2_AB9") (pintype "power_in"))
      (node (ref "U2") (pin "B10") (pinfunction "VDDQ_B10") (pintype "power_in"))
      (node (ref "U2") (pin "B3") (pinfunction "VDDQ_B3") (pintype "power_in"))
      (node (ref "U2") (pin "B5") (pinfunction "VDDQ_B5") (pintype "power_in"))
      (node (ref "U2") (pin "B8") (pinfunction "VDDQ_B8") (pintype "power_in"))
      (node (ref "U2") (pin "D1") (pinfunction "VDDQ_D1") (pintype "power_in"))
      (node (ref "U2") (pin "D12") (pinfunction "VDDQ_D12") (pintype "power_in"))
      (node (ref "U2") (pin "D5") (pinfunction "VDDQ_D5") (pintype "power_in"))
      (node (ref "U2") (pin "D8") (pinfunction "VDDQ_D8") (pintype "power_in"))
      (node (ref "U2") (pin "F10") (pinfunction "VDDQ_F10") (pintype "power_in"))
      (node (ref "U2") (pin "F3") (pinfunction "VDDQ_F3") (pintype "power_in"))
      (node (ref "U2") (pin "F5") (pinfunction "VDD2_F5") (pintype "power_in"))
      (node (ref "U2") (pin "F8") (pinfunction "VDD2_F8") (pintype "power_in"))
      (node (ref "U2") (pin "G2") (pinfunction "ODT_CA_A_G2") (pintype "input"))
      (node (ref "U2") (pin "H1") (pinfunction "VDD2_H1") (pintype "power_in"))
      (node (ref "U2") (pin "H12") (pinfunction "VDD2_H12") (pintype "power_in"))
      (node (ref "U2") (pin "H5") (pinfunction "VDD2_H5") (pintype "power_in"))
      (node (ref "U2") (pin "H8") (pinfunction "VDD2_H8") (pintype "power_in"))
      (node (ref "U2") (pin "K1") (pinfunction "VDD2_K1") (pintype "power_in"))
      (node (ref "U2") (pin "K10") (pinfunction "VDD2_K10") (pintype "power_in"))
      (node (ref "U2") (pin "K12") (pinfunction "VDD2_K12") (pintype "power_in"))
      (node (ref "U2") (pin "K3") (pinfunction "VDD2_K3") (pintype "power_in"))
      (node (ref "U2") (pin "N1") (pinfunction "VDD2_N1") (pintype "power_in"))
      (node (ref "U2") (pin "N10") (pinfunction "VDD2_N10") (pintype "power_in"))
      (node (ref "U2") (pin "N12") (pinfunction "VDD2_N12") (pintype "power_in"))
      (node (ref "U2") (pin "N3") (pinfunction "VDD2_N3") (pintype "power_in"))
      (node (ref "U2") (pin "R1") (pinfunction "VDD2_R1") (pintype "power_in"))
      (node (ref "U2") (pin "R12") (pinfunction "VDD2_R12") (pintype "power_in"))
      (node (ref "U2") (pin "R5") (pinfunction "VDD2_R5") (pintype "power_in"))
      (node (ref "U2") (pin "R8") (pinfunction "VDD2_R8") (pintype "power_in"))
      (node (ref "U2") (pin "T2") (pinfunction "ODT_CA_B_T2") (pintype "input"))
      (node (ref "U2") (pin "U10") (pinfunction "VDDQ_U10") (pintype "power_in"))
      (node (ref "U2") (pin "U3") (pinfunction "VDDQ_U3") (pintype "power_in"))
      (node (ref "U2") (pin "U5") (pinfunction "VDD2_U5") (pintype "power_in"))
      (node (ref "U2") (pin "U8") (pinfunction "VDD2_U8") (pintype "power_in"))
      (node (ref "U2") (pin "W1") (pinfunction "VDDQ_W1") (pintype "power_in"))
      (node (ref "U2") (pin "W12") (pinfunction "VDDQ_W12") (pintype "power_in"))
      (node (ref "U2") (pin "W5") (pinfunction "VDDQ_W5") (pintype "power_in"))
      (node (ref "U2") (pin "W8") (pinfunction "VDDQ_W8") (pintype "power_in"))
    )
    (net (code "71") (name "unconnected-(U1F-DDR_A1-PadAD25)") (class "Default")
      (node (ref "U1") (pin "AD25") (pinfunction "DDR_A1_AD25") (pintype "passive+no_connect"))
    )
    (net (code "72") (name "unconnected-(U1F-DDR_A7-PadAC25)") (class "Default")
      (node (ref "U1") (pin "AC25") (pinfunction "DDR_A7_AC25") (pintype "passive+no_connect"))
    )
    (net (code "73") (name "unconnected-(U1F-DDR_A13-PadK24)") (class "Default")
      (node (ref "U1") (pin "K24") (pinfunction "DDR_A13_K24") (pintype "passive+no_connect"))
    )
    (net (code "74") (name "unconnected-(U1F-DDR_A19-PadL21)") (class "Default")
      (node (ref "U1") (pin "L21") (pinfunction "DDR_A19_L21") (pintype "passive+no_connect"))
    )
    (net (code "75") (name "unconnected-(U1F-DDR_A25-PadW21)") (class "Default")
      (node (ref "U1") (pin "W21") (pinfunction "DDR_A25_W21") (pintype "passive+no_connect"))
    )
    (net (code "76") (name "unconnected-(U1F-DDR_A26-PadAB24)") (class "Default")
      (node (ref "U1") (pin "AB24") (pinfunction "DDR_A26_AB24") (pintype "passive+no_connect"))
    )
    (net (code "77") (name "unconnected-(U1F-DDR_A27-PadAA23)") (class "Default")
      (node (ref "U1") (pin "AA23") (pinfunction "DDR_A27_AA23") (pintype "passive+no_connect"))
    )
    (net (code "78") (name "unconnected-(U1F-DDR_A28-PadAC23)") (class "Default")
      (node (ref "U1") (pin "AC23") (pinfunction "DDR_A28_AC23") (pintype "passive+no_connect"))
    )
    (net (code "79") (name "unconnected-(U1F-DDR_A29-PadY22)") (class "Default")
      (node (ref "U1") (pin "Y22") (pinfunction "DDR_A29_Y22") (pintype "passive+no_connect"))
    )
    (net (code "80") (name "unconnected-(U1F-DDR_A30-PadAA21)") (class "Default")
      (node (ref "U1") (pin "AA21") (pinfunction "DDR_A30_AA21") (pintype "passive+no_connect"))
    )
    (net (code "81") (name "unconnected-(U1F-DDR_A31-PadW23)") (class "Default")
      (node (ref "U1") (pin "W23") (pinfunction "DDR_A31_W23") (pintype "passive+no_connect"))
    )
    (net (code "82") (name "unconnected-(U1F-DDR_VREF-PadG21)") (class "Default")
      (node (ref "U1") (pin "G21") (pinfunction "DDR_VREF_G21") (pintype "passive+no_connect"))
    )
    (net (code "83") (name "unconnected-(U2A-NC-PadA8)") (class "Default")
      (node (ref "U2") (pin "A8") (pinfunction "NC_A8") (pintype "input+no_connect"))
    )
    (net (code "84") (name "unconnected-(U2A-NC-PadH3)") (class "Default")
      (node (ref "U2") (pin "H3") (pinfunction "NC_H3") (pintype "input+no_connect"))
    )
    (net (code "85") (name "unconnected-(U2A-NC-PadJ5)") (class "Default")
      (node (ref "U2") (pin "J5") (pinfunction "NC_J5") (pintype "input+no_connect"))
    )
    (net (code "86") (name "unconnected-(U2A-NC-PadP5)") (class "Default")
      (node (ref "U2") (pin "P5") (pinfunction "NC_P5") (pintype "input+no_connect"))
    )
    (net (code "87") (name "unconnected-(U2A-NC-PadR3)") (class "Default")
      (node (ref "U2") (pin "R3") (pinfunction "NC_R3") (pintype "input+no_connect"))
    )
    (net (code "88") (name "unconnected-(U2B-DNU-PadA1)") (class "Default")
      (node (ref "U2") (pin "A1") (pinfunction "DNU_A1") (pintype "passive+no_connect"))
    )
    (net (code "89") (name "unconnected-(U2B-DNU-PadA2)") (class "Default")
      (node (ref "U2") (pin "A2") (pinfunction "DNU_A2") (pintype "passive+no_connect"))
    )
    (net (code "90") (name "unconnected-(U2B-DNU-PadA11)") (class "Default")
      (node (ref "U2") (pin "A11") (pinfunction "DNU_A11") (pintype "passive+no_connect"))
    )
    (net (code "91") (name "unconnected-(U2B-DNU-PadA12)") (class "Default")
      (node (ref "U2") (pin "A12") (pinfunction "DNU_A12") (pintype "passive+no_connect"))
    )
    (net (code "92") (name "unconnected-(U2B-DNU-PadAA1)") (class "Default")
      (node (ref "U2") (pin "AA1") (pinfunction "DNU_AA1") (pintype "passive+no_connect"))
    )
    (net (code "93") (name "unconnected-(U2B-DNU-PadAA12)") (class "Default")
      (node (ref "U2") (pin "AA12") (pinfunction "DNU_AA12") (pintype "passive+no_connect"))
    )
    (net (code "94") (name "unconnected-(U2B-DNU-PadAB1)") (class "Default")
      (node (ref "U2") (pin "AB1") (pinfunction "DNU_AB1") (pintype "passive+no_connect"))
    )
    (net (code "95") (name "unconnected-(U2B-DNU-PadAB2)") (class "Default")
      (node (ref "U2") (pin "AB2") (pinfunction "DNU_AB2") (pintype "passive+no_connect"))
    )
    (net (code "96") (name "unconnected-(U2B-DNU-PadAB11)") (class "Default")
      (node (ref "U2") (pin "AB11") (pinfunction "DNU_AB11") (pintype "passive+no_connect"))
    )
    (net (code "97") (name "unconnected-(U2B-DNU-PadAB12)") (class "Default")
      (node (ref "U2") (pin "AB12") (pinfunction "DNU_AB12") (pintype "passive+no_connect"))
    )
    (net (code "98") (name "unconnected-(U2B-DNU-PadB1)") (class "Default")
      (node (ref "U2") (pin "B1") (pinfunction "DNU_B1") (pintype "passive+no_connect"))
    )
    (net (code "99") (name "unconnected-(U2B-DNU-PadB12)") (class "Default")
      (node (ref "U2") (pin "B12") (pinfunction "DNU_B12") (pintype "passive+no_connect"))
    )
    (net (code "100") (name "unconnected-(U2B-NC-PadG11)") (class "Default")
      (node (ref "U2") (pin "G11") (pinfunction "NC_G11") (pintype "input+no_connect"))
    )
    (net (code "101") (name "unconnected-(U2B-NC-PadK5)") (class "Default")
      (node (ref "U2") (pin "K5") (pinfunction "NC_K5") (pintype "input+no_connect"))
    )
    (net (code "102") (name "unconnected-(U2B-NC-PadK8)") (class "Default")
      (node (ref "U2") (pin "K8") (pinfunction "NC_K8") (pintype "input+no_connect"))
    )
    (net (code "103") (name "unconnected-(U2B-NC-PadN5)") (class "Default")
      (node (ref "U2") (pin "N5") (pinfunction "NC_N5") (pintype "input+no_connect"))
    )
    (net (code "104") (name "unconnected-(U2B-NC-PadN8)") (class "Default")
      (node (ref "U2") (pin "N8") (pinfunction "NC_N8") (pintype "input+no_connect"))
    )
  )
)
